# Sheet4_LCD_Interface.net
KiCad netlist of a schematic drawn in Altium Designer
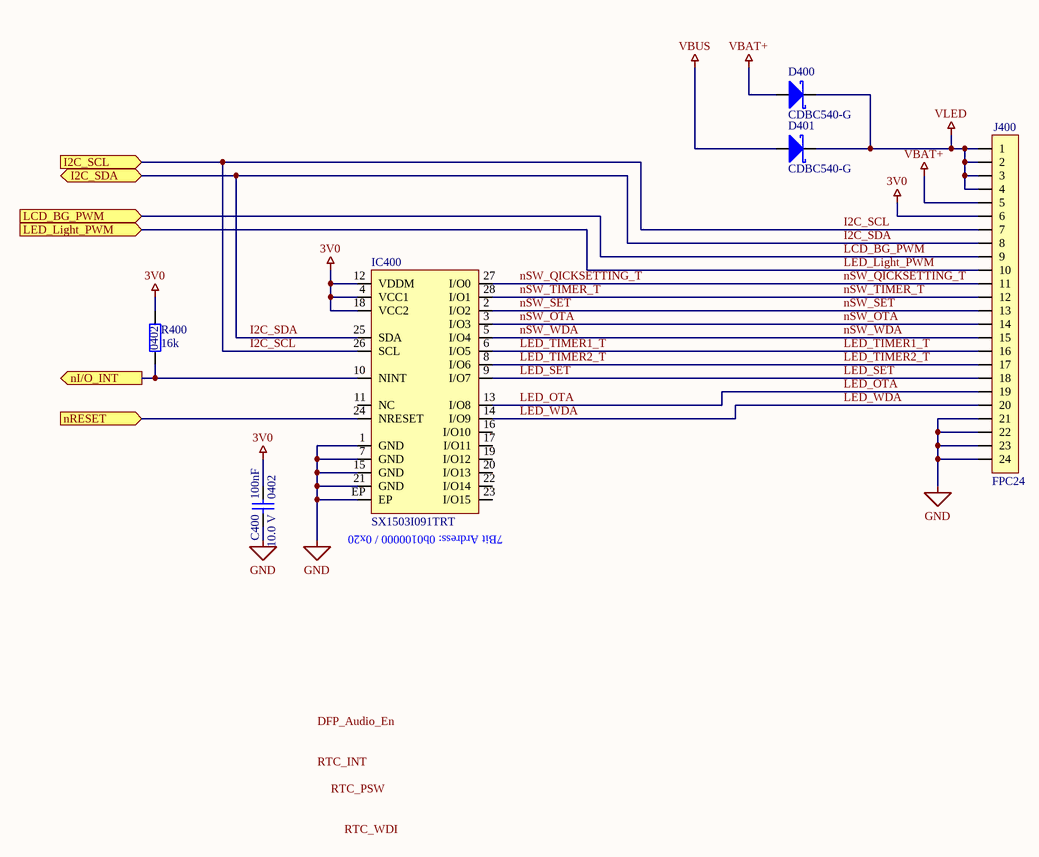
[diagram p0: Sheet4_LCD_Interface.SchDoc]

(export (version "E")
  (design (tool "Eeschema 10.0.6"))
  (components
    (comp (ref "C400")
      (value "C 100nF 0402 10V")
      (footprint "0402")
      (description "CAP CER 0.1UF 10V X5R 0402")
      (fields
        (field (name "MANUFACTURER") "Samsung Electro-Mechanics")
        (field (name "MANUFACTURER PART NUMBER") "CL05A104MP5NNNC")
        (field (name "CAPACITANCE") "100nF")
        (field (name "VOLTAGE") "10.0 V")
      )
      (libsource (lib "CS_Part_Library") (part "CAP_100nF_10V_0402"))
    )
    (comp (ref "D400")
      (value "D SCH 40V 5A")
      (footprint "DO-214AB")
      (description "DIODE SCHOTTKY 40V 5A DO214AB")
      (fields
        (field (name "MANUFACTURER") "Comchip Technology")
        (field (name "MANUFACTURER PART NUMBER") "CDBC540-G")
      )
      (libsource (lib "CS_Part_Library") (part "D_SCH_40V_5A"))
    )
    (comp (ref "D401")
      (value "D SCH 40V 5A")
      (footprint "DO-214AB")
      (description "DIODE SCHOTTKY 40V 5A DO214AB")
      (fields
        (field (name "MANUFACTURER") "Comchip Technology")
        (field (name "MANUFACTURER PART NUMBER") "CDBC540-G")
      )
      (libsource (lib "CS_Part_Library") (part "D_SCH_40V_5A"))
    )
    (comp (ref "IC400")
      (value "SX1503I091TRT")
      (footprint "UFQFN-28-EP")
      (description "IC GPIO EXPANDER I2C 16CH 28-QFN")
      (fields (field (name "MANUFACTURER") "Semtech Corporation"))
      (libsource (lib "CS_Part_Library") (part "IC_16ch_Port_Extender_2"))
    )
    (comp (ref "J400")
      (value "FPC24")
      (footprint "J_FPC_522712479")
      (description "CONN FPC BOT 24 PIN 1mm Pitch")
      (fields (field (name "MANUFACTURER") "MOLEX") (field (name "MANUFACTURER PART NUMBER") "522712479"))
      (libsource (lib "Symbols") (part "J_FPC24_DS"))
    )
    (comp (ref "R400")
      (value "R 16k 0402")
      (footprint "0402")
      (description "RES 16K OHM 1% 1/16W 0402")
      (fields
        (field (name "MANUFACTURER") "Stackpole Electronics Inc")
        (field (name "MANUFACTURER PART NUMBER") "RMCF0402FT16K0")
        (field (name "RESISTANCE") "16k")
      )
      (libsource (lib "CS_Part_Library") (part "R_16k_0402"))
    )
  )
  (nets
    (net (code "2") (name "/I2C_SCL") (class "Default")
      (node (ref "IC400") (pin "26") (pinfunction "SCL_26") (pintype "passive"))
      (node (ref "J400") (pin "7") (pinfunction "7_7") (pintype "passive"))
    )
    (net (code "3") (name "/I2C_SDA") (class "Default")
      (node (ref "IC400") (pin "25") (pinfunction "SDA_25") (pintype "passive"))
      (node (ref "J400") (pin "8") (pinfunction "8_8") (pintype "passive"))
    )
    (net (code "4") (name "/LCD_BG_PWM") (class "Default")
      (node (ref "J400") (pin "9") (pinfunction "9_9") (pintype "passive"))
    )
    (net (code "5") (name "/LED_Light_PWM") (class "Default")
      (node (ref "J400") (pin "10") (pinfunction "10_10") (pintype "passive"))
    )
    (net (code "6") (name "/LED_OTA") (class "Default")
      (node (ref "IC400") (pin "13") (pinfunction "I/O8_13") (pintype "passive"))
      (node (ref "J400") (pin "19") (pinfunction "19_19") (pintype "passive"))
    )
    (net (code "7") (name "/LED_SET") (class "Default")
      (node (ref "IC400") (pin "9") (pinfunction "I/O7_9") (pintype "passive"))
      (node (ref "J400") (pin "18") (pinfunction "18_18") (pintype "passive"))
    )
    (net (code "8") (name "/LED_TIMER1_T") (class "Default")
      (node (ref "IC400") (pin "6") (pinfunction "I/O5_6") (pintype "passive"))
      (node (ref "J400") (pin "16") (pinfunction "16_16") (pintype "passive"))
    )
    (net (code "9") (name "/LED_TIMER2_T") (class "Default")
      (node (ref "IC400") (pin "8") (pinfunction "I/O6_8") (pintype "passive"))
      (node (ref "J400") (pin "17") (pinfunction "17_17") (pintype "passive"))
    )
    (net (code "10") (name "/LED_WDA") (class "Default")
      (node (ref "IC400") (pin "14") (pinfunction "I/O9_14") (pintype "passive"))
      (node (ref "J400") (pin "20") (pinfunction "20_20") (pintype "passive"))
    )
    (net (code "14") (name "/nI{slash}O_INT") (class "Default")
      (node (ref "IC400") (pin "10") (pinfunction "NINT_10") (pintype "passive"))
      (node (ref "R400") (pin "1") (pinfunction "1_1") (pintype "passive"))
    )
    (net (code "15") (name "/nRESET") (class "Default")
      (node (ref "IC400") (pin "24") (pinfunction "NRESET_24") (pintype "passive"))
    )
    (net (code "16") (name "/nSW_OTA") (class "Default")
      (node (ref "IC400") (pin "3") (pinfunction "I/O3_3") (pintype "passive"))
      (node (ref "J400") (pin "14") (pinfunction "14_14") (pintype "passive"))
    )
    (net (code "17") (name "/nSW_QICKSETTING_T") (class "Default")
      (node (ref "IC400") (pin "27") (pinfunction "I/O0_27") (pintype "passive"))
      (node (ref "J400") (pin "11") (pinfunction "11_11") (pintype "passive"))
    )
    (net (code "18") (name "/nSW_SET") (class "Default")
      (node (ref "IC400") (pin "2") (pinfunction "I/O2_2") (pintype "passive"))
      (node (ref "J400") (pin "13") (pinfunction "13_13") (pintype "passive"))
    )
    (net (code "19") (name "/nSW_TIMER_T") (class "Default")
      (node (ref "IC400") (pin "28") (pinfunction "I/O1_28") (pintype "passive"))
      (node (ref "J400") (pin "12") (pinfunction "12_12") (pintype "passive"))
    )
    (net (code "20") (name "/nSW_WDA") (class "Default")
      (node (ref "IC400") (pin "5") (pinfunction "I/O4_5") (pintype "passive"))
      (node (ref "J400") (pin "15") (pinfunction "15_15") (pintype "passive"))
    )
    (net (code "21") (name "3V0") (class "Default")
      (node (ref "C400") (pin "2") (pinfunction "2_2") (pintype "passive"))
      (node (ref "IC400") (pin "12") (pinfunction "VDDM_12") (pintype "passive"))
      (node (ref "IC400") (pin "18") (pinfunction "VCC2_18") (pintype "passive"))
      (node (ref "IC400") (pin "4") (pinfunction "VCC1_4") (pintype "passive"))
      (node (ref "J400") (pin "6") (pinfunction "6_6") (pintype "passive"))
      (node (ref "R400") (pin "2") (pinfunction "2_2") (pintype "passive"))
    )
    (net (code "22") (name "GND") (class "Default")
      (node (ref "C400") (pin "1") (pinfunction "1_1") (pintype "passive"))
      (node (ref "IC400") (pin "1") (pinfunction "GND_1") (pintype "passive"))
      (node (ref "IC400") (pin "15") (pinfunction "GND_15") (pintype "passive"))
      (node (ref "IC400") (pin "21") (pinfunction "GND_21") (pintype "passive"))
      (node (ref "IC400") (pin "7") (pinfunction "GND_7") (pintype "passive"))
      (node (ref "IC400") (pin "EP") (pinfunction "EP_EP") (pintype "passive"))
      (node (ref "J400") (pin "21") (pinfunction "21_21") (pintype "passive"))
      (node (ref "J400") (pin "22") (pinfunction "22_22") (pintype "passive"))
      (node (ref "J400") (pin "23") (pinfunction "23_23") (pintype "passive"))
      (node (ref "J400") (pin "24") (pinfunction "24_24") (pintype "passive"))
    )
    (net (code "23") (name "VBAT+") (class "Default")
      (node (ref "D400") (pin "2") (pinfunction "A_2") (pintype "passive"))
      (node (ref "J400") (pin "5") (pinfunction "5_5") (pintype "passive"))
    )
    (net (code "24") (name "VBUS") (class "Default")
      (node (ref "D401") (pin "2") (pinfunction "A_2") (pintype "passive"))
    )
    (net (code "25") (name "VLED") (class "Default")
      (node (ref "D400") (pin "1") (pinfunction "K_1") (pintype "passive"))
      (node (ref "D401") (pin "1") (pinfunction "K_1") (pintype "passive"))
      (node (ref "J400") (pin "1") (pinfunction "1_1") (pintype "passive"))
      (node (ref "J400") (pin "2") (pinfunction "2_2") (pintype "passive"))
      (node (ref "J400") (pin "3") (pinfunction "3_3") (pintype "passive"))
      (node (ref "J400") (pin "4") (pinfunction "4_4") (pintype "passive"))
    )
    (net (code "26") (name "unconnected-(IC400-I{slash}O10-Pad16)") (class "Default")
      (node (ref "IC400") (pin "16") (pinfunction "I/O10_16") (pintype "passive"))
    )
    (net (code "27") (name "unconnected-(IC400-I{slash}O11-Pad17)") (class "Default")
      (node (ref "IC400") (pin "17") (pinfunction "I/O11_17") (pintype "passive"))
    )
    (net (code "28") (name "unconnected-(IC400-I{slash}O12-Pad19)") (class "Default")
      (node (ref "IC400") (pin "19") (pinfunction "I/O12_19") (pintype "passive"))
    )
    (net (code "29") (name "unconnected-(IC400-I{slash}O13-Pad20)") (class "Default")
      (node (ref "IC400") (pin "20") (pinfunction "I/O13_20") (pintype "passive"))
    )
    (net (code "30") (name "unconnected-(IC400-I{slash}O14-Pad22)") (class "Default")
      (node (ref "IC400") (pin "22") (pinfunction "I/O14_22") (pintype "passive"))
    )
    (net (code "31") (name "unconnected-(IC400-I{slash}O15-Pad23)") (class "Default")
      (node (ref "IC400") (pin "23") (pinfunction "I/O15_23") (pintype "passive"))
    )
    (net (code "32") (name "unconnected-(IC400-NC-Pad11)") (class "Default")
      (node (ref "IC400") (pin "11") (pinfunction "NC_11") (pintype "passive"))
    )
  )
)
